# IMU_9DoF_Fusion.net
KiCad netlist of a schematic drawn in EAGLE
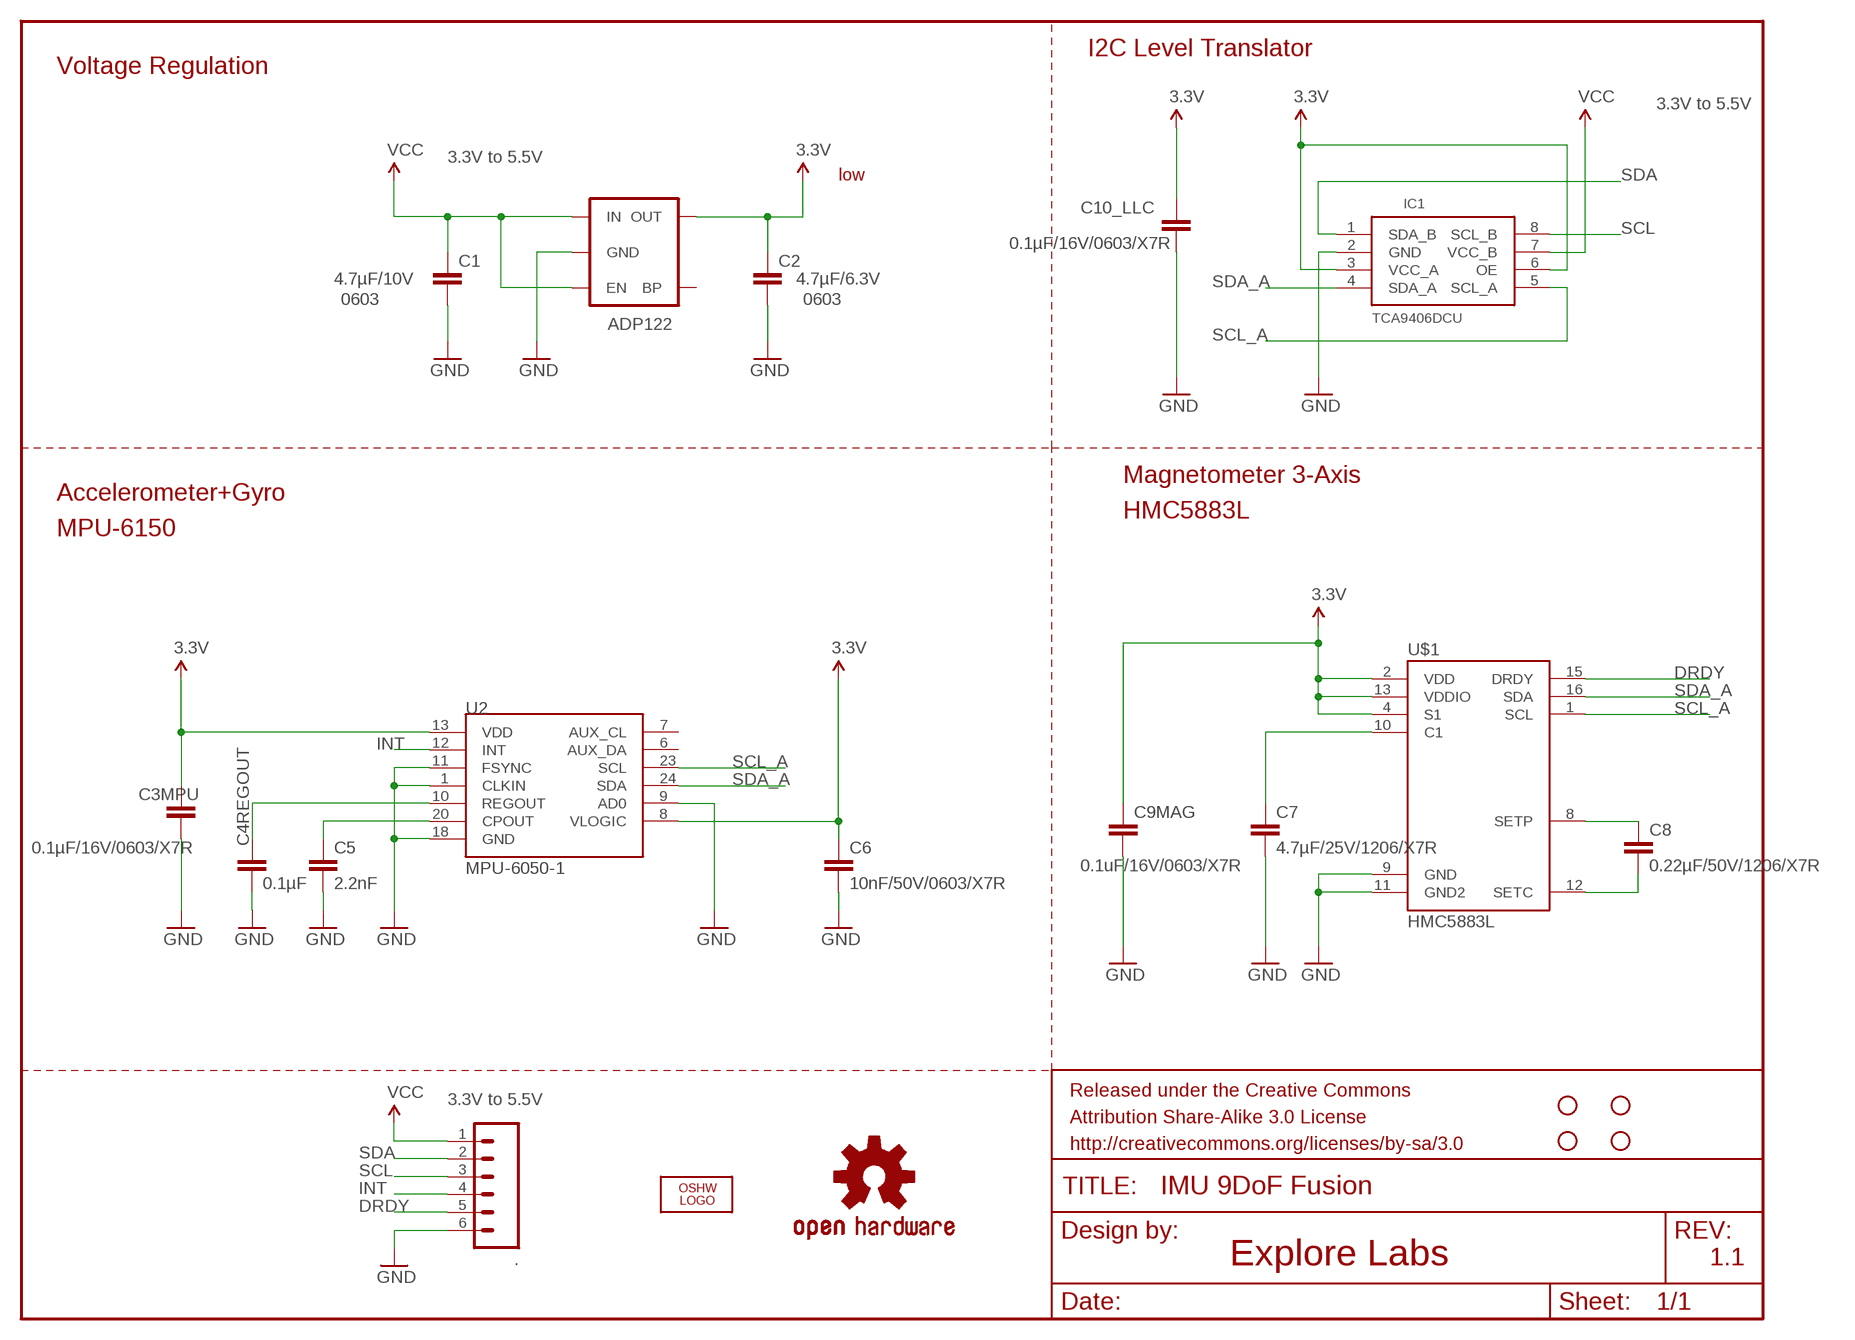
[diagram p0: schematic, sheet 1]

(export (version "E")
  (design (tool "Eeschema 10.0.6"))
  (components
    (comp (ref ".")
      (value "M06SIP")
      (footprint "eagle-import:1X06")
      (libsource (lib "eagle-import") (part "M06SIP"))
    )
    (comp (ref "ADP122")
      (value "V_REG_LDOSMD")
      (footprint "eagle-import:SOT23-5")
      (libsource (lib "eagle-import") (part "V_REG_LDOSMD"))
    )
    (comp (ref "C1")
      (value "4.7µF/10V")
      (footprint "eagle-import:0603-CAP")
      (libsource (lib "eagle-import") (part "CAP0603-CAP"))
    )
    (comp (ref "C2")
      (value "4.7µF/6.3V")
      (footprint "eagle-import:0603-CAP")
      (libsource (lib "eagle-import") (part "CAP0603-CAP"))
    )
    (comp (ref "C3MPU")
      (value "0.1µF/16V/0603/X7R")
      (footprint "eagle-import:0603-CAP")
      (libsource (lib "eagle-import") (part "CAP0603-CAP"))
    )
    (comp (ref "C4REGOUT")
      (value "0.1µF")
      (footprint "eagle-import:0603-CAP")
      (libsource (lib "eagle-import") (part "CAP0603-CAP"))
    )
    (comp (ref "C5")
      (value "2.2nF")
      (footprint "eagle-import:0603-CAP")
      (libsource (lib "eagle-import") (part "CAP0603-CAP"))
    )
    (comp (ref "C6")
      (value "10nF/50V/0603/X7R")
      (footprint "eagle-import:0603-CAP")
      (libsource (lib "eagle-import") (part "CAP0603-CAP"))
    )
    (comp (ref "C7")
      (value "4.7µF/25V/1206/X7R")
      (footprint "eagle-import:1206")
      (libsource (lib "eagle-import") (part "CAP1206"))
    )
    (comp (ref "C8")
      (value "0.22µF/50V/1206/X7R")
      (footprint "eagle-import:1206")
      (libsource (lib "eagle-import") (part "CAP1206"))
    )
    (comp (ref "C9MAG")
      (value "0.1uF/16V/0603/X7R")
      (footprint "eagle-import:0603-CAP")
      (libsource (lib "eagle-import") (part "CAP0603-CAP"))
    )
    (comp (ref "C10_LLC")
      (value "0.1µF/16V/0603/X7R")
      (footprint "eagle-import:0603-CAP")
      (libsource (lib "eagle-import") (part "CAP0603-CAP"))
    )
    (comp (ref "IC1")
      (value "TCA9406DCU")
      (footprint "eagle-import:VSSOP8")
      (libsource (lib "eagle-import") (part "TCA9406DCU"))
    )
    (comp (ref "JP1")
      (value "STAND-OFFTIGHT")
      (footprint "eagle-import:STAND-OFF-TIGHT")
      (libsource (lib "eagle-import") (part "STAND-OFFTIGHT"))
    )
    (comp (ref "JP3")
      (value "STAND-OFFTIGHT")
      (footprint "eagle-import:STAND-OFF-TIGHT")
      (libsource (lib "eagle-import") (part "STAND-OFFTIGHT"))
    )
    (comp (ref "JP4")
      (value "STAND-OFFTIGHT")
      (footprint "eagle-import:STAND-OFF-TIGHT")
      (libsource (lib "eagle-import") (part "STAND-OFFTIGHT"))
    )
    (comp (ref "JP5")
      (value "STAND-OFFTIGHT")
      (footprint "eagle-import:STAND-OFF-TIGHT")
      (libsource (lib "eagle-import") (part "STAND-OFFTIGHT"))
    )
    (comp (ref "LOGO1")
      (value "OSHW_LOGO_FILLX0150-NT")
      (footprint "eagle-import:OSHW_FILLX150_NOTEXT")
      (libsource (lib "eagle-import") (part "OSHW_LOGO_FILLX0150-NT"))
    )
    (comp (ref "U$1")
      (value "HMC5883L")
      (footprint "eagle-import:LPCC16")
      (libsource (lib "eagle-import") (part "HMC5883L"))
    )
    (comp (ref "U$2")
      (value "OSHW-LOGOS")
      (footprint "eagle-import:OSHW-LOGO-S")
      (libsource (lib "eagle-import") (part "OSHW-LOGOS"))
    )
    (comp (ref "U2")
      (value "MPU-6050-1")
      (footprint "eagle-import:QFN-24-4MM2")
      (libsource (lib "eagle-import") (part "MPU-6050-1"))
    )
  )
  (nets
    (net (code "1") (name "/DRDY") (class "Default")
      (node (ref ".") (pin "5") (pinfunction "5_5") (pintype "passive"))
      (node (ref "U$1") (pin "15") (pinfunction "DRDY_15") (pintype "bidirectional"))
    )
    (net (code "2") (name "/INT") (class "Default")
      (node (ref ".") (pin "4") (pinfunction "4_4") (pintype "passive"))
      (node (ref "U2") (pin "12") (pinfunction "INT_12") (pintype "bidirectional"))
    )
    (net (code "3") (name "/SCL") (class "Default")
      (node (ref ".") (pin "3") (pinfunction "3_3") (pintype "passive"))
      (node (ref "IC1") (pin "8") (pinfunction "SCL_B_8") (pintype "bidirectional"))
    )
    (net (code "4") (name "/SCL_A") (class "Default")
      (node (ref "IC1") (pin "5") (pinfunction "SCL_A_5") (pintype "bidirectional"))
      (node (ref "U$1") (pin "1") (pinfunction "SCL_1") (pintype "bidirectional"))
      (node (ref "U2") (pin "23") (pinfunction "SCL_23") (pintype "bidirectional"))
    )
    (net (code "5") (name "/SDA") (class "Default")
      (node (ref ".") (pin "2") (pinfunction "2_2") (pintype "passive"))
      (node (ref "IC1") (pin "1") (pinfunction "SDA_B_1") (pintype "bidirectional"))
    )
    (net (code "6") (name "/SDA_A") (class "Default")
      (node (ref "IC1") (pin "4") (pinfunction "SDA_A_4") (pintype "bidirectional"))
      (node (ref "U$1") (pin "16") (pinfunction "SDA_16") (pintype "bidirectional"))
      (node (ref "U2") (pin "24") (pinfunction "SDA_24") (pintype "bidirectional"))
    )
    (net (code "7") (name "3.3V") (class "Default")
      (node (ref "ADP122") (pin "5") (pinfunction "OUT_5") (pintype "passive"))
      (node (ref "C10_LLC") (pin "1") (pinfunction "1_1") (pintype "passive"))
      (node (ref "C2") (pin "1") (pinfunction "1_1") (pintype "passive"))
      (node (ref "C3MPU") (pin "1") (pinfunction "1_1") (pintype "passive"))
      (node (ref "C6") (pin "1") (pinfunction "1_1") (pintype "passive"))
      (node (ref "C9MAG") (pin "1") (pinfunction "1_1") (pintype "passive"))
      (node (ref "IC1") (pin "3") (pinfunction "VCC_A_3") (pintype "power_in"))
      (node (ref "IC1") (pin "6") (pinfunction "OE_6") (pintype "input"))
      (node (ref "U$1") (pin "13") (pinfunction "VDDIO_13") (pintype "bidirectional"))
      (node (ref "U$1") (pin "2") (pinfunction "VDD_2") (pintype "bidirectional"))
      (node (ref "U$1") (pin "4") (pinfunction "S1_4") (pintype "bidirectional"))
      (node (ref "U2") (pin "13") (pinfunction "VDD_13") (pintype "bidirectional"))
      (node (ref "U2") (pin "8") (pinfunction "VLOGIC_8") (pintype "bidirectional"))
    )
    (net (code "8") (name "GND") (class "Default")
      (node (ref ".") (pin "6") (pinfunction "6_6") (pintype "passive"))
      (node (ref "ADP122") (pin "2") (pinfunction "GND_2") (pintype "input"))
      (node (ref "C1") (pin "2") (pinfunction "2_2") (pintype "passive"))
      (node (ref "C10_LLC") (pin "2") (pinfunction "2_2") (pintype "passive"))
      (node (ref "C2") (pin "2") (pinfunction "2_2") (pintype "passive"))
      (node (ref "C3MPU") (pin "2") (pinfunction "2_2") (pintype "passive"))
      (node (ref "C4REGOUT") (pin "2") (pinfunction "2_2") (pintype "passive"))
      (node (ref "C5") (pin "2") (pinfunction "2_2") (pintype "passive"))
      (node (ref "C6") (pin "2") (pinfunction "2_2") (pintype "passive"))
      (node (ref "C7") (pin "2") (pinfunction "2_2") (pintype "passive"))
      (node (ref "C9MAG") (pin "2") (pinfunction "2_2") (pintype "passive"))
      (node (ref "IC1") (pin "2") (pinfunction "GND_2") (pintype "power_in"))
      (node (ref "U$1") (pin "11") (pinfunction "GND2_11") (pintype "bidirectional"))
      (node (ref "U$1") (pin "9") (pinfunction "GND_9") (pintype "bidirectional"))
      (node (ref "U2") (pin "1") (pinfunction "CLKIN_1") (pintype "bidirectional"))
      (node (ref "U2") (pin "11") (pinfunction "FSYNC_11") (pintype "bidirectional"))
      (node (ref "U2") (pin "18") (pinfunction "GND_18") (pintype "bidirectional"))
      (node (ref "U2") (pin "9") (pinfunction "AD0_9") (pintype "bidirectional"))
    )
    (net (code "9") (name "Net-(U$1-C1)") (class "Default")
      (node (ref "C7") (pin "1") (pinfunction "1_1") (pintype "passive"))
      (node (ref "U$1") (pin "10") (pinfunction "C1_10") (pintype "bidirectional"))
    )
    (net (code "10") (name "Net-(U$1-SETC)") (class "Default")
      (node (ref "C8") (pin "2") (pinfunction "2_2") (pintype "passive"))
      (node (ref "U$1") (pin "12") (pinfunction "SETC_12") (pintype "bidirectional"))
    )
    (net (code "11") (name "Net-(U$1-SETP)") (class "Default")
      (node (ref "C8") (pin "1") (pinfunction "1_1") (pintype "passive"))
      (node (ref "U$1") (pin "8") (pinfunction "SETP_8") (pintype "bidirectional"))
    )
    (net (code "12") (name "Net-(U2-CPOUT)") (class "Default")
      (node (ref "C5") (pin "1") (pinfunction "1_1") (pintype "passive"))
      (node (ref "U2") (pin "20") (pinfunction "CPOUT_20") (pintype "bidirectional"))
    )
    (net (code "13") (name "Net-(U2-REGOUT)") (class "Default")
      (node (ref "C4REGOUT") (pin "1") (pinfunction "1_1") (pintype "passive"))
      (node (ref "U2") (pin "10") (pinfunction "REGOUT_10") (pintype "bidirectional"))
    )
    (net (code "14") (name "VCC") (class "Default")
      (node (ref ".") (pin "1") (pinfunction "1_1") (pintype "passive"))
      (node (ref "ADP122") (pin "1") (pinfunction "IN_1") (pintype "input"))
      (node (ref "ADP122") (pin "3") (pinfunction "EN_3") (pintype "input"))
      (node (ref "C1") (pin "1") (pinfunction "1_1") (pintype "passive"))
      (node (ref "IC1") (pin "7") (pinfunction "VCC_B_7") (pintype "power_in"))
    )
    (net (code "15") (name "unconnected-(ADP122-BP-Pad4)") (class "Default")
      (node (ref "ADP122") (pin "4") (pinfunction "BP_4") (pintype "input"))
    )
    (net (code "16") (name "unconnected-(U2-AUX_CL-Pad7)") (class "Default")
      (node (ref "U2") (pin "7") (pinfunction "AUX_CL_7") (pintype "bidirectional"))
    )
    (net (code "17") (name "unconnected-(U2-AUX_DA-Pad6)") (class "Default")
      (node (ref "U2") (pin "6") (pinfunction "AUX_DA_6") (pintype "bidirectional"))
    )
  )
)
